# B134B.net
KiCad netlist of a schematic drawn in EAGLE
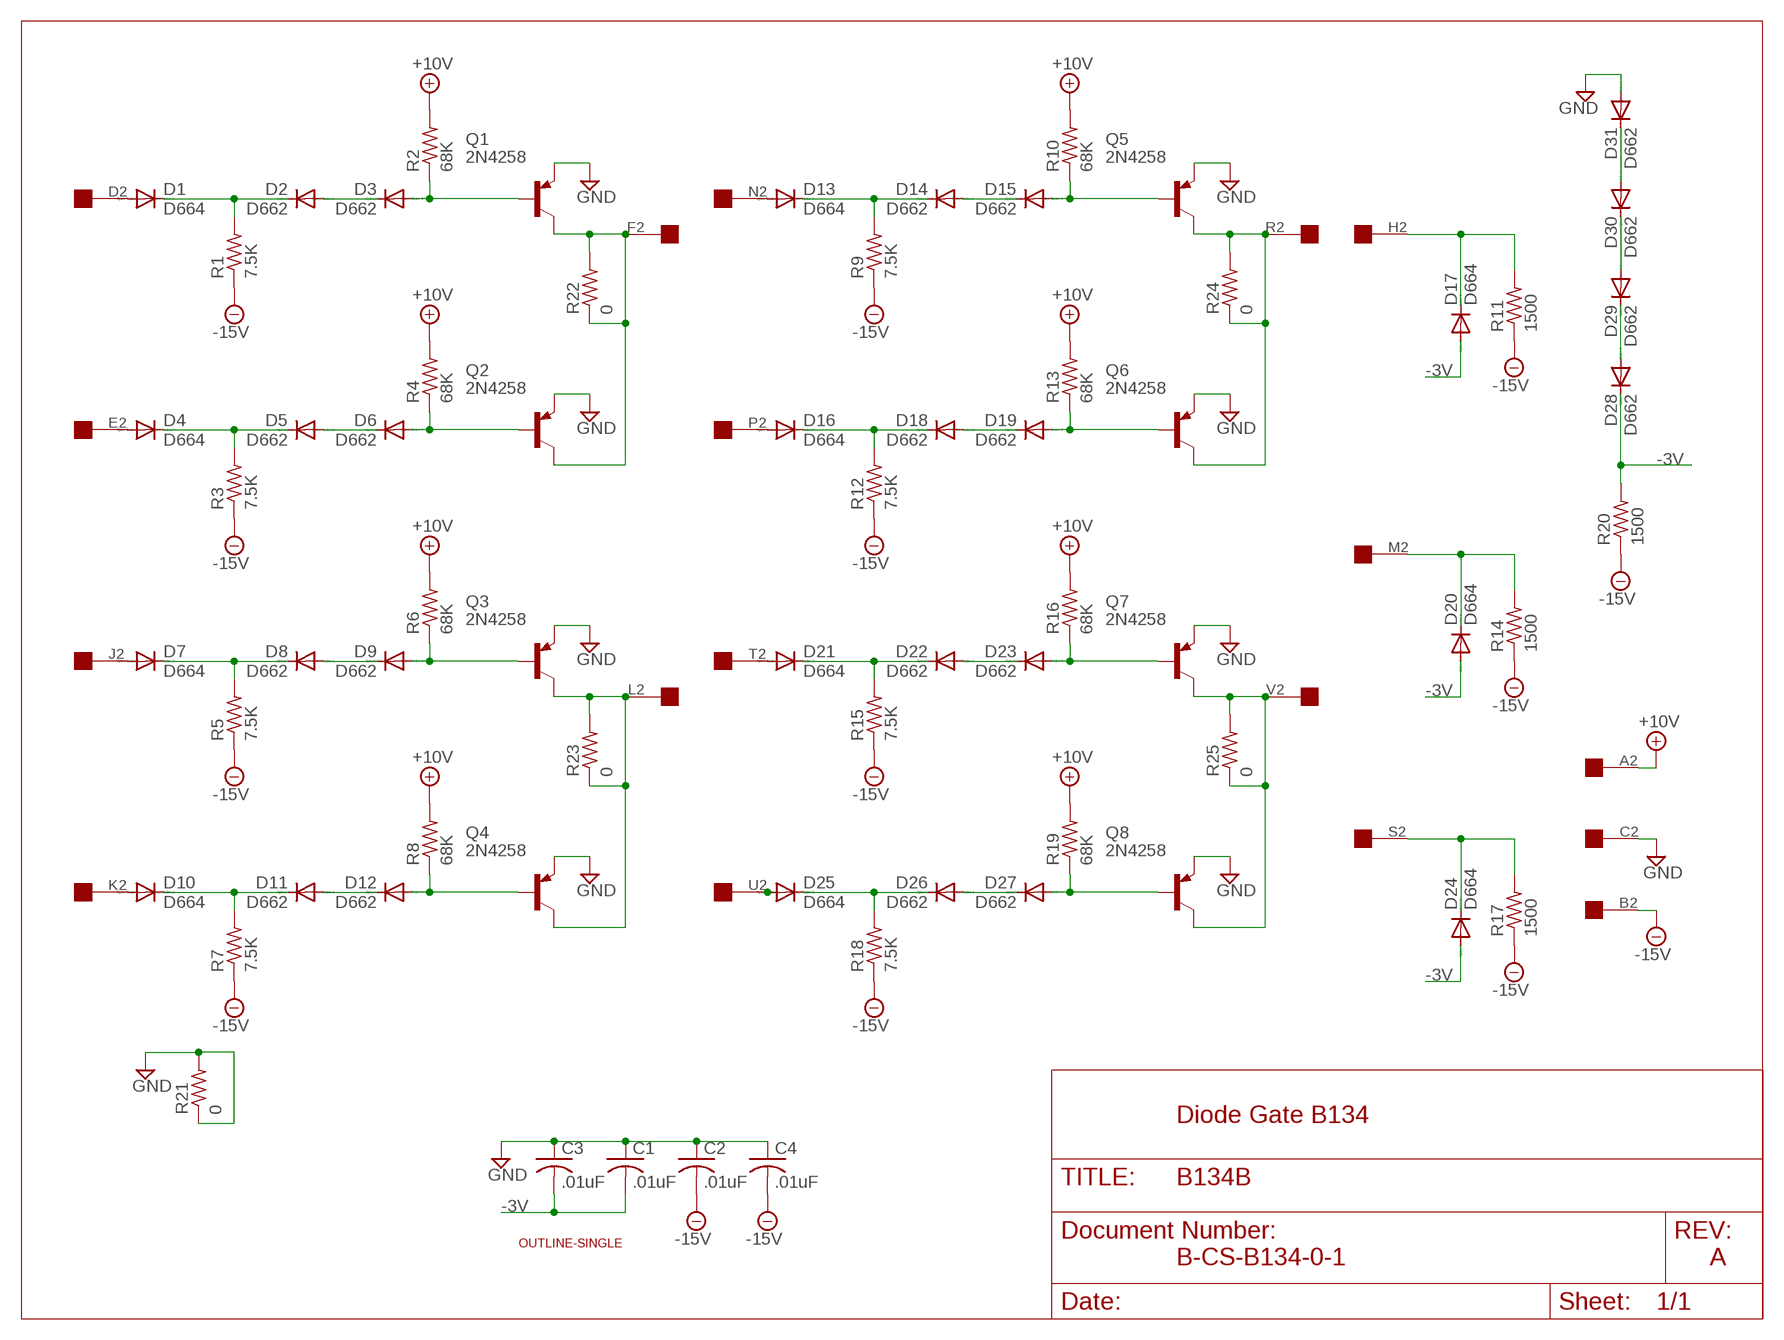
[diagram p0: schematic, sheet 1]

(export (version "E")
  (design (tool "Eeschema 10.0.6"))
  (components
    (comp (ref "C1")
      (value ".01uF")
      (footprint "eagle-import:C063-025X075")
      (libsource (lib "eagle-import") (part "C-US"))
    )
    (comp (ref "C2")
      (value ".01uF")
      (footprint "eagle-import:C063-025X075")
      (libsource (lib "eagle-import") (part "C-US"))
    )
    (comp (ref "C3")
      (value ".01uF")
      (footprint "eagle-import:C063-025X075")
      (libsource (lib "eagle-import") (part "C-US"))
    )
    (comp (ref "C4")
      (value ".01uF")
      (footprint "eagle-import:C063-025X075")
      (libsource (lib "eagle-import") (part "C-US"))
    )
    (comp (ref "D1")
      (value "D664")
      (footprint "eagle-import:DO35-10")
      (libsource (lib "eagle-import") (part "DIODE-DO35-10"))
    )
    (comp (ref "D2")
      (value "D662")
      (footprint "eagle-import:DO35-10")
      (libsource (lib "eagle-import") (part "DIODE-DO35-10"))
    )
    (comp (ref "D3")
      (value "D662")
      (footprint "eagle-import:DO35-10")
      (libsource (lib "eagle-import") (part "DIODE-DO35-10"))
    )
    (comp (ref "D4")
      (value "D664")
      (footprint "eagle-import:DO35-10")
      (libsource (lib "eagle-import") (part "DIODE-DO35-10"))
    )
    (comp (ref "D5")
      (value "D662")
      (footprint "eagle-import:DO35-10")
      (libsource (lib "eagle-import") (part "DIODE-DO35-10"))
    )
    (comp (ref "D6")
      (value "D662")
      (footprint "eagle-import:DO35-10")
      (libsource (lib "eagle-import") (part "DIODE-DO35-10"))
    )
    (comp (ref "D7")
      (value "D664")
      (footprint "eagle-import:DO35-10")
      (libsource (lib "eagle-import") (part "DIODE-DO35-10"))
    )
    (comp (ref "D8")
      (value "D662")
      (footprint "eagle-import:DO35-10")
      (libsource (lib "eagle-import") (part "DIODE-DO35-10"))
    )
    (comp (ref "D9")
      (value "D662")
      (footprint "eagle-import:DO35-10")
      (libsource (lib "eagle-import") (part "DIODE-DO35-10"))
    )
    (comp (ref "D10")
      (value "D664")
      (footprint "eagle-import:DO35-10")
      (libsource (lib "eagle-import") (part "DIODE-DO35-10"))
    )
    (comp (ref "D11")
      (value "D662")
      (footprint "eagle-import:DO35-10")
      (libsource (lib "eagle-import") (part "DIODE-DO35-10"))
    )
    (comp (ref "D12")
      (value "D662")
      (footprint "eagle-import:DO35-10")
      (libsource (lib "eagle-import") (part "DIODE-DO35-10"))
    )
    (comp (ref "D13")
      (value "D664")
      (footprint "eagle-import:DO35-10")
      (libsource (lib "eagle-import") (part "DIODE-DO35-10"))
    )
    (comp (ref "D14")
      (value "D662")
      (footprint "eagle-import:DO35-10")
      (libsource (lib "eagle-import") (part "DIODE-DO35-10"))
    )
    (comp (ref "D15")
      (value "D662")
      (footprint "eagle-import:DO35-10")
      (libsource (lib "eagle-import") (part "DIODE-DO35-10"))
    )
    (comp (ref "D16")
      (value "D664")
      (footprint "eagle-import:DO35-10")
      (libsource (lib "eagle-import") (part "DIODE-DO35-10"))
    )
    (comp (ref "D17")
      (value "D664")
      (footprint "eagle-import:DO35-10")
      (libsource (lib "eagle-import") (part "DIODE-DO35-10"))
    )
    (comp (ref "D18")
      (value "D662")
      (footprint "eagle-import:DO35-10")
      (libsource (lib "eagle-import") (part "DIODE-DO35-10"))
    )
    (comp (ref "D19")
      (value "D662")
      (footprint "eagle-import:DO35-10")
      (libsource (lib "eagle-import") (part "DIODE-DO35-10"))
    )
    (comp (ref "D20")
      (value "D664")
      (footprint "eagle-import:DO35-10")
      (libsource (lib "eagle-import") (part "DIODE-DO35-10"))
    )
    (comp (ref "D21")
      (value "D664")
      (footprint "eagle-import:DO35-10")
      (libsource (lib "eagle-import") (part "DIODE-DO35-10"))
    )
    (comp (ref "D22")
      (value "D662")
      (footprint "eagle-import:DO35-10")
      (libsource (lib "eagle-import") (part "DIODE-DO35-10"))
    )
    (comp (ref "D23")
      (value "D662")
      (footprint "eagle-import:DO35-10")
      (libsource (lib "eagle-import") (part "DIODE-DO35-10"))
    )
    (comp (ref "D24")
      (value "D664")
      (footprint "eagle-import:DO35-10")
      (libsource (lib "eagle-import") (part "DIODE-DO35-10"))
    )
    (comp (ref "D25")
      (value "D664")
      (footprint "eagle-import:DO35-10")
      (libsource (lib "eagle-import") (part "DIODE-DO35-10"))
    )
    (comp (ref "D26")
      (value "D662")
      (footprint "eagle-import:DO35-10")
      (libsource (lib "eagle-import") (part "DIODE-DO35-10"))
    )
    (comp (ref "D27")
      (value "D662")
      (footprint "eagle-import:DO35-10")
      (libsource (lib "eagle-import") (part "DIODE-DO35-10"))
    )
    (comp (ref "D28")
      (value "D662")
      (footprint "eagle-import:DO35-10")
      (libsource (lib "eagle-import") (part "DIODE-DO35-10"))
    )
    (comp (ref "D29")
      (value "D662")
      (footprint "eagle-import:DO35-10")
      (libsource (lib "eagle-import") (part "DIODE-DO35-10"))
    )
    (comp (ref "D30")
      (value "D662")
      (footprint "eagle-import:DO35-10")
      (libsource (lib "eagle-import") (part "DIODE-DO35-10"))
    )
    (comp (ref "D31")
      (value "D662")
      (footprint "eagle-import:DO35-10")
      (libsource (lib "eagle-import") (part "DIODE-DO35-10"))
    )
    (comp (ref "Q1")
      (value "2N4258")
      (footprint "eagle-import:TO5")
      (libsource (lib "eagle-import") (part "-PNP-TO5"))
    )
    (comp (ref "Q2")
      (value "2N4258")
      (footprint "eagle-import:TO5")
      (libsource (lib "eagle-import") (part "-PNP-TO5"))
    )
    (comp (ref "Q3")
      (value "2N4258")
      (footprint "eagle-import:TO5")
      (libsource (lib "eagle-import") (part "-PNP-TO5"))
    )
    (comp (ref "Q4")
      (value "2N4258")
      (footprint "eagle-import:TO5")
      (libsource (lib "eagle-import") (part "-PNP-TO5"))
    )
    (comp (ref "Q5")
      (value "2N4258")
      (footprint "eagle-import:TO5")
      (libsource (lib "eagle-import") (part "-PNP-TO5"))
    )
    (comp (ref "Q6")
      (value "2N4258")
      (footprint "eagle-import:TO5")
      (libsource (lib "eagle-import") (part "-PNP-TO5"))
    )
    (comp (ref "Q7")
      (value "2N4258")
      (footprint "eagle-import:TO5")
      (libsource (lib "eagle-import") (part "-PNP-TO5"))
    )
    (comp (ref "Q8")
      (value "2N4258")
      (footprint "eagle-import:TO5")
      (libsource (lib "eagle-import") (part "-PNP-TO5"))
    )
    (comp (ref "R1")
      (value "7.5K")
      (footprint "eagle-import:0207_10")
      (libsource (lib "eagle-import") (part "R-US_0207/10"))
    )
    (comp (ref "R2")
      (value "68K")
      (footprint "eagle-import:0207_10")
      (libsource (lib "eagle-import") (part "R-US_0207/10"))
    )
    (comp (ref "R3")
      (value "7.5K")
      (footprint "eagle-import:0207_10")
      (libsource (lib "eagle-import") (part "R-US_0207/10"))
    )
    (comp (ref "R4")
      (value "68K")
      (footprint "eagle-import:0207_10")
      (libsource (lib "eagle-import") (part "R-US_0207/10"))
    )
    (comp (ref "R5")
      (value "7.5K")
      (footprint "eagle-import:0207_10")
      (libsource (lib "eagle-import") (part "R-US_0207/10"))
    )
    (comp (ref "R6")
      (value "68K")
      (footprint "eagle-import:0207_10")
      (libsource (lib "eagle-import") (part "R-US_0207/10"))
    )
    (comp (ref "R7")
      (value "7.5K")
      (footprint "eagle-import:0207_10")
      (libsource (lib "eagle-import") (part "R-US_0207/10"))
    )
    (comp (ref "R8")
      (value "68K")
      (footprint "eagle-import:0207_10")
      (libsource (lib "eagle-import") (part "R-US_0207/10"))
    )
    (comp (ref "R9")
      (value "7.5K")
      (footprint "eagle-import:0207_10")
      (libsource (lib "eagle-import") (part "R-US_0207/10"))
    )
    (comp (ref "R10")
      (value "68K")
      (footprint "eagle-import:0207_10")
      (libsource (lib "eagle-import") (part "R-US_0207/10"))
    )
    (comp (ref "R11")
      (value "1500")
      (footprint "eagle-import:0207_10")
      (libsource (lib "eagle-import") (part "R-US_0207/10"))
    )
    (comp (ref "R12")
      (value "7.5K")
      (footprint "eagle-import:0207_10")
      (libsource (lib "eagle-import") (part "R-US_0207/10"))
    )
    (comp (ref "R13")
      (value "68K")
      (footprint "eagle-import:0207_10")
      (libsource (lib "eagle-import") (part "R-US_0207/10"))
    )
    (comp (ref "R14")
      (value "1500")
      (footprint "eagle-import:0207_10")
      (libsource (lib "eagle-import") (part "R-US_0207/10"))
    )
    (comp (ref "R15")
      (value "7.5K")
      (footprint "eagle-import:0207_10")
      (libsource (lib "eagle-import") (part "R-US_0207/10"))
    )
    (comp (ref "R16")
      (value "68K")
      (footprint "eagle-import:0207_10")
      (libsource (lib "eagle-import") (part "R-US_0207/10"))
    )
    (comp (ref "R17")
      (value "1500")
      (footprint "eagle-import:0207_10")
      (libsource (lib "eagle-import") (part "R-US_0207/10"))
    )
    (comp (ref "R18")
      (value "7.5K")
      (footprint "eagle-import:0207_10")
      (libsource (lib "eagle-import") (part "R-US_0207/10"))
    )
    (comp (ref "R19")
      (value "68K")
      (footprint "eagle-import:0207_10")
      (libsource (lib "eagle-import") (part "R-US_0207/10"))
    )
    (comp (ref "R20")
      (value "1500")
      (footprint "eagle-import:0207_10")
      (libsource (lib "eagle-import") (part "R-US_0207/10"))
    )
    (comp (ref "R21")
      (value "0")
      (footprint "eagle-import:0207_10")
      (libsource (lib "eagle-import") (part "R-US_0207/10"))
    )
    (comp (ref "R22")
      (value "0")
      (footprint "eagle-import:0207_10")
      (libsource (lib "eagle-import") (part "R-US_0207/10"))
    )
    (comp (ref "R23")
      (value "0")
      (footprint "eagle-import:0207_10")
      (libsource (lib "eagle-import") (part "R-US_0207/10"))
    )
    (comp (ref "R24")
      (value "0")
      (footprint "eagle-import:0207_10")
      (libsource (lib "eagle-import") (part "R-US_0207/10"))
    )
    (comp (ref "R25")
      (value "0")
      (footprint "eagle-import:0207_10")
      (libsource (lib "eagle-import") (part "R-US_0207/10"))
    )
    (comp (ref "U$1")
      (value "OUTLINE-SINGLE")
      (footprint "eagle-import:SINGLE")
      (libsource (lib "eagle-import") (part "OUTLINE-SINGLE"))
    )
    (comp (ref "U$2")
      (value "EDGE-1")
      (footprint "eagle-import:EDGE-CON1")
      (libsource (lib "eagle-import") (part "EDGE-1"))
    )
  )
  (nets
    (net (code "1") (name "+10V") (class "Default")
      (node (ref "R10") (pin "2") (pinfunction "2_2") (pintype "passive"))
      (node (ref "R13") (pin "2") (pinfunction "2_2") (pintype "passive"))
      (node (ref "R16") (pin "2") (pinfunction "2_2") (pintype "passive"))
      (node (ref "R19") (pin "2") (pinfunction "2_2") (pintype "passive"))
      (node (ref "R2") (pin "2") (pinfunction "2_2") (pintype "passive"))
      (node (ref "R4") (pin "2") (pinfunction "2_2") (pintype "passive"))
      (node (ref "R6") (pin "2") (pinfunction "2_2") (pintype "passive"))
      (node (ref "R8") (pin "2") (pinfunction "2_2") (pintype "passive"))
      (node (ref "U$2") (pin "A2") (pinfunction "1_A2") (pintype "bidirectional"))
    )
    (net (code "2") (name "-15V") (class "Default")
      (node (ref "C2") (pin "2") (pinfunction "2_2") (pintype "passive"))
      (node (ref "C4") (pin "2") (pinfunction "2_2") (pintype "passive"))
      (node (ref "R1") (pin "1") (pinfunction "1_1") (pintype "passive"))
      (node (ref "R11") (pin "1") (pinfunction "1_1") (pintype "passive"))
      (node (ref "R12") (pin "1") (pinfunction "1_1") (pintype "passive"))
      (node (ref "R14") (pin "1") (pinfunction "1_1") (pintype "passive"))
      (node (ref "R15") (pin "1") (pinfunction "1_1") (pintype "passive"))
      (node (ref "R17") (pin "1") (pinfunction "1_1") (pintype "passive"))
      (node (ref "R18") (pin "1") (pinfunction "1_1") (pintype "passive"))
      (node (ref "R20") (pin "1") (pinfunction "1_1") (pintype "passive"))
      (node (ref "R3") (pin "1") (pinfunction "1_1") (pintype "passive"))
      (node (ref "R5") (pin "1") (pinfunction "1_1") (pintype "passive"))
      (node (ref "R7") (pin "1") (pinfunction "1_1") (pintype "passive"))
      (node (ref "R9") (pin "1") (pinfunction "1_1") (pintype "passive"))
      (node (ref "U$2") (pin "B2") (pinfunction "1_B2") (pintype "bidirectional"))
    )
    (net (code "3") (name "/-3V") (class "Default")
      (node (ref "C1") (pin "2") (pinfunction "2_2") (pintype "passive"))
      (node (ref "C3") (pin "2") (pinfunction "2_2") (pintype "passive"))
      (node (ref "D17") (pin "A") (pinfunction "A_A") (pintype "passive"))
      (node (ref "D20") (pin "A") (pinfunction "A_A") (pintype "passive"))
      (node (ref "D24") (pin "A") (pinfunction "A_A") (pintype "passive"))
      (node (ref "D28") (pin "C") (pinfunction "C_C") (pintype "passive"))
      (node (ref "R20") (pin "2") (pinfunction "2_2") (pintype "passive"))
    )
    (net (code "4") (name "GND") (class "Default")
      (node (ref "C1") (pin "1") (pinfunction "1_1") (pintype "passive"))
      (node (ref "C2") (pin "1") (pinfunction "1_1") (pintype "passive"))
      (node (ref "C3") (pin "1") (pinfunction "1_1") (pintype "passive"))
      (node (ref "C4") (pin "1") (pinfunction "1_1") (pintype "passive"))
      (node (ref "D31") (pin "A") (pinfunction "A_A") (pintype "passive"))
      (node (ref "Q1") (pin "1") (pinfunction "E_1") (pintype "passive"))
      (node (ref "Q2") (pin "1") (pinfunction "E_1") (pintype "passive"))
      (node (ref "Q3") (pin "1") (pinfunction "E_1") (pintype "passive"))
      (node (ref "Q4") (pin "1") (pinfunction "E_1") (pintype "passive"))
      (node (ref "Q5") (pin "1") (pinfunction "E_1") (pintype "passive"))
      (node (ref "Q6") (pin "1") (pinfunction "E_1") (pintype "passive"))
      (node (ref "Q7") (pin "1") (pinfunction "E_1") (pintype "passive"))
      (node (ref "Q8") (pin "1") (pinfunction "E_1") (pintype "passive"))
      (node (ref "R21") (pin "1") (pinfunction "1_1") (pintype "passive"))
      (node (ref "R21") (pin "2") (pinfunction "2_2") (pintype "passive"))
      (node (ref "U$2") (pin "C2") (pinfunction "1_C2") (pintype "bidirectional"))
    )
    (net (code "5") (name "Net-(D1-PadC)") (class "Default")
      (node (ref "D1") (pin "C") (pinfunction "C_C") (pintype "passive"))
      (node (ref "D2") (pin "C") (pinfunction "C_C") (pintype "passive"))
      (node (ref "R1") (pin "2") (pinfunction "2_2") (pintype "passive"))
    )
    (net (code "6") (name "Net-(D2-PadA)") (class "Default")
      (node (ref "D2") (pin "A") (pinfunction "A_A") (pintype "passive"))
      (node (ref "D3") (pin "C") (pinfunction "C_C") (pintype "passive"))
    )
    (net (code "7") (name "Net-(D4-PadC)") (class "Default")
      (node (ref "D4") (pin "C") (pinfunction "C_C") (pintype "passive"))
      (node (ref "D5") (pin "C") (pinfunction "C_C") (pintype "passive"))
      (node (ref "R3") (pin "2") (pinfunction "2_2") (pintype "passive"))
    )
    (net (code "8") (name "Net-(D5-PadA)") (class "Default")
      (node (ref "D5") (pin "A") (pinfunction "A_A") (pintype "passive"))
      (node (ref "D6") (pin "C") (pinfunction "C_C") (pintype "passive"))
    )
    (net (code "9") (name "Net-(D7-PadC)") (class "Default")
      (node (ref "D7") (pin "C") (pinfunction "C_C") (pintype "passive"))
      (node (ref "D8") (pin "C") (pinfunction "C_C") (pintype "passive"))
      (node (ref "R5") (pin "2") (pinfunction "2_2") (pintype "passive"))
    )
    (net (code "10") (name "Net-(D8-PadA)") (class "Default")
      (node (ref "D8") (pin "A") (pinfunction "A_A") (pintype "passive"))
      (node (ref "D9") (pin "C") (pinfunction "C_C") (pintype "passive"))
    )
    (net (code "11") (name "Net-(D10-PadC)") (class "Default")
      (node (ref "D10") (pin "C") (pinfunction "C_C") (pintype "passive"))
      (node (ref "D11") (pin "C") (pinfunction "C_C") (pintype "passive"))
      (node (ref "R7") (pin "2") (pinfunction "2_2") (pintype "passive"))
    )
    (net (code "12") (name "Net-(D11-PadA)") (class "Default")
      (node (ref "D11") (pin "A") (pinfunction "A_A") (pintype "passive"))
      (node (ref "D12") (pin "C") (pinfunction "C_C") (pintype "passive"))
    )
    (net (code "13") (name "Net-(D13-PadC)") (class "Default")
      (node (ref "D13") (pin "C") (pinfunction "C_C") (pintype "passive"))
      (node (ref "D14") (pin "C") (pinfunction "C_C") (pintype "passive"))
      (node (ref "R9") (pin "2") (pinfunction "2_2") (pintype "passive"))
    )
    (net (code "14") (name "Net-(D14-PadA)") (class "Default")
      (node (ref "D14") (pin "A") (pinfunction "A_A") (pintype "passive"))
      (node (ref "D15") (pin "C") (pinfunction "C_C") (pintype "passive"))
    )
    (net (code "15") (name "Net-(D16-PadC)") (class "Default")
      (node (ref "D16") (pin "C") (pinfunction "C_C") (pintype "passive"))
      (node (ref "D18") (pin "C") (pinfunction "C_C") (pintype "passive"))
      (node (ref "R12") (pin "2") (pinfunction "2_2") (pintype "passive"))
    )
    (net (code "16") (name "Net-(D18-PadA)") (class "Default")
      (node (ref "D18") (pin "A") (pinfunction "A_A") (pintype "passive"))
      (node (ref "D19") (pin "C") (pinfunction "C_C") (pintype "passive"))
    )
    (net (code "17") (name "Net-(D21-PadC)") (class "Default")
      (node (ref "D21") (pin "C") (pinfunction "C_C") (pintype "passive"))
      (node (ref "D22") (pin "C") (pinfunction "C_C") (pintype "passive"))
      (node (ref "R15") (pin "2") (pinfunction "2_2") (pintype "passive"))
    )
    (net (code "18") (name "Net-(D22-PadA)") (class "Default")
      (node (ref "D22") (pin "A") (pinfunction "A_A") (pintype "passive"))
      (node (ref "D23") (pin "C") (pinfunction "C_C") (pintype "passive"))
    )
    (net (code "19") (name "Net-(D25-PadC)") (class "Default")
      (node (ref "D25") (pin "C") (pinfunction "C_C") (pintype "passive"))
      (node (ref "D26") (pin "C") (pinfunction "C_C") (pintype "passive"))
      (node (ref "R18") (pin "2") (pinfunction "2_2") (pintype "passive"))
    )
    (net (code "20") (name "Net-(D26-PadA)") (class "Default")
      (node (ref "D26") (pin "A") (pinfunction "A_A") (pintype "passive"))
      (node (ref "D27") (pin "C") (pinfunction "C_C") (pintype "passive"))
    )
    (net (code "21") (name "Net-(D28-PadA)") (class "Default")
      (node (ref "D28") (pin "A") (pinfunction "A_A") (pintype "passive"))
      (node (ref "D29") (pin "C") (pinfunction "C_C") (pintype "passive"))
    )
    (net (code "22") (name "Net-(D29-PadA)") (class "Default")
      (node (ref "D29") (pin "A") (pinfunction "A_A") (pintype "passive"))
      (node (ref "D30") (pin "C") (pinfunction "C_C") (pintype "passive"))
    )
    (net (code "23") (name "Net-(D30-PadA)") (class "Default")
      (node (ref "D30") (pin "A") (pinfunction "A_A") (pintype "passive"))
      (node (ref "D31") (pin "C") (pinfunction "C_C") (pintype "passive"))
    )
    (net (code "24") (name "Net-(Q1-B)") (class "Default")
      (node (ref "D3") (pin "A") (pinfunction "A_A") (pintype "passive"))
      (node (ref "Q1") (pin "2") (pinfunction "B_2") (pintype "passive"))
      (node (ref "R2") (pin "1") (pinfunction "1_1") (pintype "passive"))
    )
    (net (code "25") (name "Net-(Q1-C)") (class "Default")
      (node (ref "Q1") (pin "3") (pinfunction "C_3") (pintype "passive"))
      (node (ref "Q2") (pin "3") (pinfunction "C_3") (pintype "passive"))
      (node (ref "R22") (pin "1") (pinfunction "1_1") (pintype "passive"))
      (node (ref "R22") (pin "2") (pinfunction "2_2") (pintype "passive"))
      (node (ref "U$2") (pin "F2") (pinfunction "1_F2") (pintype "bidirectional"))
    )
    (net (code "26") (name "Net-(Q2-B)") (class "Default")
      (node (ref "D6") (pin "A") (pinfunction "A_A") (pintype "passive"))
      (node (ref "Q2") (pin "2") (pinfunction "B_2") (pintype "passive"))
      (node (ref "R4") (pin "1") (pinfunction "1_1") (pintype "passive"))
    )
    (net (code "27") (name "Net-(Q3-B)") (class "Default")
      (node (ref "D9") (pin "A") (pinfunction "A_A") (pintype "passive"))
      (node (ref "Q3") (pin "2") (pinfunction "B_2") (pintype "passive"))
      (node (ref "R6") (pin "1") (pinfunction "1_1") (pintype "passive"))
    )
    (net (code "28") (name "Net-(Q3-C)") (class "Default")
      (node (ref "Q3") (pin "3") (pinfunction "C_3") (pintype "passive"))
      (node (ref "Q4") (pin "3") (pinfunction "C_3") (pintype "passive"))
      (node (ref "R23") (pin "1") (pinfunction "1_1") (pintype "passive"))
      (node (ref "R23") (pin "2") (pinfunction "2_2") (pintype "passive"))
      (node (ref "U$2") (pin "L2") (pinfunction "1_L2") (pintype "bidirectional"))
    )
    (net (code "29") (name "Net-(Q4-B)") (class "Default")
      (node (ref "D12") (pin "A") (pinfunction "A_A") (pintype "passive"))
      (node (ref "Q4") (pin "2") (pinfunction "B_2") (pintype "passive"))
      (node (ref "R8") (pin "1") (pinfunction "1_1") (pintype "passive"))
    )
    (net (code "30") (name "Net-(Q5-B)") (class "Default")
      (node (ref "D15") (pin "A") (pinfunction "A_A") (pintype "passive"))
      (node (ref "Q5") (pin "2") (pinfunction "B_2") (pintype "passive"))
      (node (ref "R10") (pin "1") (pinfunction "1_1") (pintype "passive"))
    )
    (net (code "31") (name "Net-(Q5-C)") (class "Default")
      (node (ref "Q5") (pin "3") (pinfunction "C_3") (pintype "passive"))
      (node (ref "Q6") (pin "3") (pinfunction "C_3") (pintype "passive"))
      (node (ref "R24") (pin "1") (pinfunction "1_1") (pintype "passive"))
      (node (ref "R24") (pin "2") (pinfunction "2_2") (pintype "passive"))
      (node (ref "U$2") (pin "R2") (pinfunction "1_R2") (pintype "bidirectional"))
    )
    (net (code "32") (name "Net-(Q6-B)") (class "Default")
      (node (ref "D19") (pin "A") (pinfunction "A_A") (pintype "passive"))
      (node (ref "Q6") (pin "2") (pinfunction "B_2") (pintype "passive"))
      (node (ref "R13") (pin "1") (pinfunction "1_1") (pintype "passive"))
    )
    (net (code "33") (name "Net-(Q7-B)") (class "Default")
      (node (ref "D23") (pin "A") (pinfunction "A_A") (pintype "passive"))
      (node (ref "Q7") (pin "2") (pinfunction "B_2") (pintype "passive"))
      (node (ref "R16") (pin "1") (pinfunction "1_1") (pintype "passive"))
    )
    (net (code "34") (name "Net-(Q7-C)") (class "Default")
      (node (ref "Q7") (pin "3") (pinfunction "C_3") (pintype "passive"))
      (node (ref "Q8") (pin "3") (pinfunction "C_3") (pintype "passive"))
      (node (ref "R25") (pin "1") (pinfunction "1_1") (pintype "passive"))
      (node (ref "R25") (pin "2") (pinfunction "2_2") (pintype "passive"))
      (node (ref "U$2") (pin "V2") (pinfunction "1_V2") (pintype "bidirectional"))
    )
    (net (code "35") (name "Net-(Q8-B)") (class "Default")
      (node (ref "D27") (pin "A") (pinfunction "A_A") (pintype "passive"))
      (node (ref "Q8") (pin "2") (pinfunction "B_2") (pintype "passive"))
      (node (ref "R19") (pin "1") (pinfunction "1_1") (pintype "passive"))
    )
    (net (code "36") (name "Net-(U$2D-1)") (class "Default")
      (node (ref "D1") (pin "A") (pinfunction "A_A") (pintype "passive"))
      (node (ref "U$2") (pin "D2") (pinfunction "1_D2") (pintype "bidirectional"))
    )
    (net (code "37") (name "Net-(U$2E-1)") (class "Default")
      (node (ref "D4") (pin "A") (pinfunction "A_A") (pintype "passive"))
      (node (ref "U$2") (pin "E2") (pinfunction "1_E2") (pintype "bidirectional"))
    )
    (net (code "38") (name "Net-(U$2G-1)") (class "Default")
      (node (ref "D17") (pin "C") (pinfunction "C_C") (pintype "passive"))
      (node (ref "R11") (pin "2") (pinfunction "2_2") (pintype "passive"))
      (node (ref "U$2") (pin "H2") (pinfunction "1_H2") (pintype "bidirectional"))
    )
    (net (code "39") (name "Net-(U$2H-1)") (class "Default")
      (node (ref "D7") (pin "A") (pinfunction "A_A") (pintype "passive"))
      (node (ref "U$2") (pin "J2") (pinfunction "1_J2") (pintype "bidirectional"))
    )
    (net (code "40") (name "Net-(U$2I-1)") (class "Default")
      (node (ref "D10") (pin "A") (pinfunction "A_A") (pintype "passive"))
      (node (ref "U$2") (pin "K2") (pinfunction "1_K2") (pintype "bidirectional"))
    )
    (net (code "41") (name "Net-(U$2K-1)") (class "Default")
      (node (ref "D20") (pin "C") (pinfunction "C_C") (pintype "passive"))
      (node (ref "R14") (pin "2") (pinfunction "2_2") (pintype "passive"))
      (node (ref "U$2") (pin "M2") (pinfunction "1_M2") (pintype "bidirectional"))
    )
    (net (code "42") (name "Net-(U$2L-1)") (class "Default")
      (node (ref "D13") (pin "A") (pinfunction "A_A") (pintype "passive"))
      (node (ref "U$2") (pin "N2") (pinfunction "1_N2") (pintype "bidirectional"))
    )
    (net (code "43") (name "Net-(U$2M-1)") (class "Default")
      (node (ref "D16") (pin "A") (pinfunction "A_A") (pintype "passive"))
      (node (ref "U$2") (pin "P2") (pinfunction "1_P2") (pintype "bidirectional"))
    )
    (net (code "44") (name "Net-(U$2O-1)") (class "Default")
      (node (ref "D24") (pin "C") (pinfunction "C_C") (pintype "passive"))
      (node (ref "R17") (pin "2") (pinfunction "2_2") (pintype "passive"))
      (node (ref "U$2") (pin "S2") (pinfunction "1_S2") (pintype "bidirectional"))
    )
    (net (code "45") (name "Net-(U$2P-1)") (class "Default")
      (node (ref "D21") (pin "A") (pinfunction "A_A") (pintype "passive"))
      (node (ref "U$2") (pin "T2") (pinfunction "1_T2") (pintype "bidirectional"))
    )
    (net (code "46") (name "Net-(U$2Q-1)") (class "Default")
      (node (ref "D25") (pin "A") (pinfunction "A_A") (pintype "passive"))
      (node (ref "U$2") (pin "U2") (pinfunction "1_U2") (pintype "bidirectional"))
    )
  )
)
